# Power.net
KiCad netlist of a schematic drawn in Altium Designer
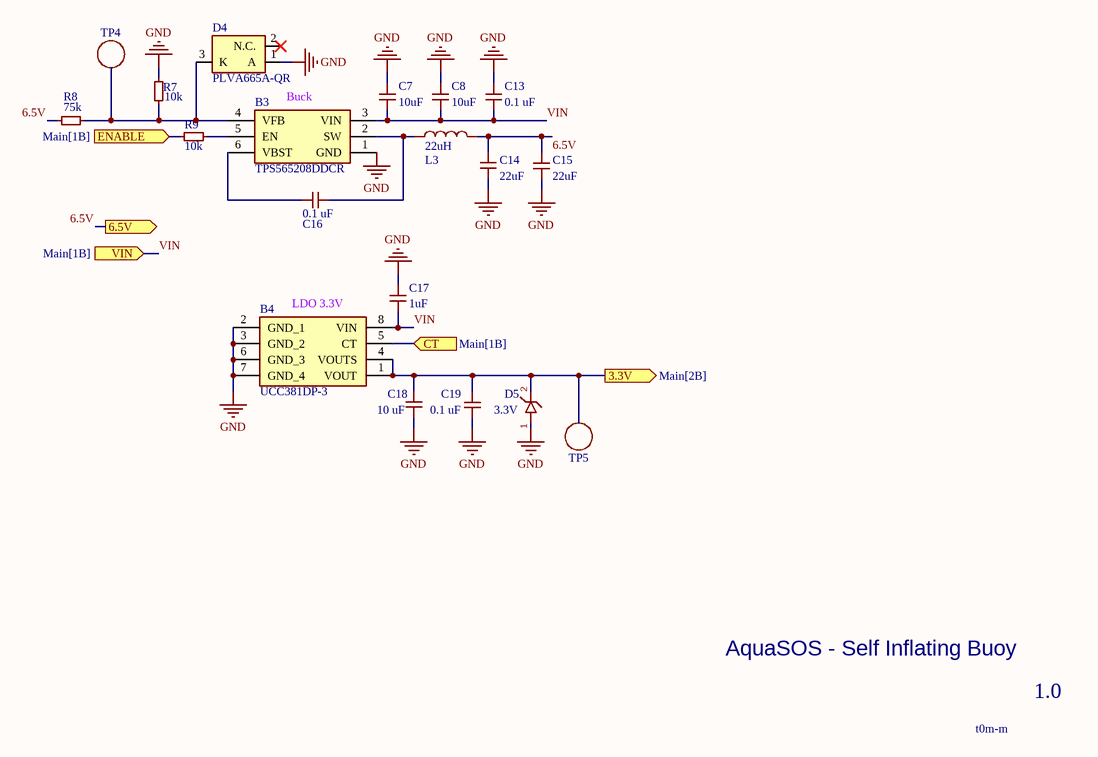
[diagram p0: Power.SchDoc]

(export (version "E")
  (design (tool "Eeschema 10.0.6"))
  (components
    (comp (ref "B3")
      (value "TPS565208DDCR")
      (footprint "SOT95P280X110-6N")
      (description "4.5V to 17V, 5A Synchronous Step-Down Voltage Regulator in SOT23")
      (fields (field (name "MOUSER PART NUMBER") "595-TPS565208DDCR"))
      (libsource (lib "Schlib1") (part "TPS565208DDCR"))
    )
    (comp (ref "B4")
      (value "UCC381DP-3")
      (footprint "UCC381DP-3-8N")
      (description "1-A, Low-Dropout Linear Regulator")
      (fields (field (name "MOUSER PART NUMBER") "595-UCC381DP-3"))
      (libsource (lib "Schlib1") (part "UCC381DP-3"))
    )
    (comp (ref "C7")
      (value "10uF")
      (footprint "CAPC2012X145N")
      (libsource (lib "Schlib1") (part "C0805X106K8RACAUTO7210"))
    )
    (comp (ref "C8")
      (value "10uF")
      (footprint "CAPC2012X145N")
      (libsource (lib "Schlib1") (part "C0805X106K8RACAUTO7210"))
    )
    (comp (ref "C13")
      (value "0.1 uF")
      (footprint "MLASU105SB7104KFNB25")
      (description "0.1uF Capacitor")
      (libsource (lib "Schlib1") (part "MLASU105SB7104KFNB25"))
    )
    (comp (ref "C14")
      (value "22uF")
      (footprint "CL31X226KPHN3NE")
      (description "CAP CER 22UF 10V X6S 1206")
      (libsource (lib "Schlib1") (part "CL31X226KPHN3NE"))
    )
    (comp (ref "C15")
      (value "22uF")
      (footprint "CL31X226KPHN3NE")
      (description "CAP CER 22UF 10V X6S 1206")
      (libsource (lib "Schlib1") (part "CL31X226KPHN3NE"))
    )
    (comp (ref "C16")
      (value "0.1 uF")
      (footprint "MLASU105SB7104KFNB25")
      (description "0.1uF Capacitor")
      (libsource (lib "Schlib1") (part "MLASU105SB7104KFNB25"))
    )
    (comp (ref "C17")
      (value "1uF")
      (footprint "MLASU105SB7104KFNB25")
      (description "1uF 0402 10V")
      (libsource (lib "Schlib1") (part "GRM155Z71A105KE01D"))
    )
    (comp (ref "C18")
      (value "10 uF")
      (footprint "KGM05CS60J106MH")
      (description "10 uF Capacitor")
      (libsource (lib "Schlib1") (part "KGM05CS60J106MH"))
    )
    (comp (ref "C19")
      (value "0.1 uF")
      (footprint "MLASU105SB7104KFNB25")
      (description "0.1uF Capacitor")
      (libsource (lib "Schlib1") (part "MLASU105SB7104KFNB25"))
    )
    (comp (ref "D4")
      (value "PLVA665A-QR")
      (footprint "PLVA665A-QR")
      (description "Zener Diode 6.5 V 250 mW +/-3.08% Surface Mount TO-236AB")
      (fields (field (name "MOUSER PART NUMBER") "771-PLVA665A-QR"))
      (libsource (lib "AquaSOS DevBoard") (part "PLVA665A-QR"))
    )
    (comp (ref "D5")
      (value "3.3V")
      (footprint "MMSZ5226C-HE3_A-08")
      (description "3.3V Zener Diode")
      (libsource (lib "AquaSOS DevBoard") (part "MMSZ5226C-HE3_A-08"))
    )
    (comp (ref "L3")
      (value "22uH")
      (footprint "SRR1240-3R3Y")
      (libsource (lib "Schlib1") (part "SRR1240-3R3Y"))
    )
    (comp (ref "R7")
      (value "10k")
      (footprint "CRCW040210K0FKEDC")
      (description "10k 0402 Resistor")
      (libsource (lib "") (part "CRCW040210K0FKEDC_1"))
    )
    (comp (ref "R8")
      (value "75k")
      (footprint "CRCW040210K0FKEDC")
      (libsource (lib "Schlib1") (part "RT73F1E75KBTH"))
    )
    (comp (ref "R9")
      (value "10k")
      (footprint "CRCW040210K0FKEDC")
      (description "10k 0402 Resistor")
      (libsource (lib "AquaSOS DevBoard") (part "CRCW040210K0FKEDC"))
    )
    (comp (ref "TP4")
      (value "TP")
      (footprint "Test Point")
      (description "Test Point")
      (libsource (lib "AquaSOS DevBoard") (part "Test Point"))
    )
    (comp (ref "TP5")
      (value "TP")
      (footprint "Test Point")
      (description "Test Point")
      (libsource (lib "AquaSOS DevBoard") (part "Test Point"))
    )
  )
  (nets
    (net (code "1") (name "/3.3V") (class "Default")
      (node (ref "B4") (pin "1") (pinfunction "VOUT_1") (pintype "passive"))
      (node (ref "B4") (pin "4") (pinfunction "VOUTS_4") (pintype "passive"))
      (node (ref "C18") (pin "1") (pinfunction "1_1") (pintype "passive"))
      (node (ref "C19") (pin "1") (pinfunction "1_1") (pintype "passive"))
      (node (ref "D5") (pin "2") (pinfunction "A_2") (pintype "passive"))
      (node (ref "TP5") (pin "1") (pinfunction "1_1") (pintype "passive"))
    )
    (net (code "2") (name "/6.5V") (class "Default")
      (node (ref "C14") (pin "1") (pinfunction "1_1") (pintype "passive"))
      (node (ref "C15") (pin "1") (pinfunction "1_1") (pintype "passive"))
      (node (ref "L3") (pin "2") (pinfunction "2_2") (pintype "passive"))
      (node (ref "R8") (pin "1") (pinfunction "1_1") (pintype "passive"))
    )
    (net (code "3") (name "/CT") (class "Default")
      (node (ref "B4") (pin "5") (pinfunction "CT_5") (pintype "passive"))
    )
    (net (code "4") (name "/ENABLE") (class "Default")
      (node (ref "R9") (pin "1") (pinfunction "1_1") (pintype "passive"))
    )
    (net (code "5") (name "/VIN") (class "Default")
      (node (ref "B3") (pin "3") (pinfunction "VIN_3") (pintype "passive"))
      (node (ref "B4") (pin "8") (pinfunction "VIN_8") (pintype "passive"))
      (node (ref "C13") (pin "2") (pinfunction "2_2") (pintype "passive"))
      (node (ref "C17") (pin "2") (pinfunction "2_2") (pintype "passive"))
      (node (ref "C7") (pin "1") (pinfunction "1_1") (pintype "passive"))
      (node (ref "C8") (pin "1") (pinfunction "1_1") (pintype "passive"))
    )
    (net (code "6") (name "GND") (class "Default")
      (node (ref "B3") (pin "1") (pinfunction "GND_1") (pintype "passive"))
      (node (ref "B4") (pin "2") (pinfunction "GND_1_2") (pintype "passive"))
      (node (ref "B4") (pin "3") (pinfunction "GND_2_3") (pintype "passive"))
      (node (ref "B4") (pin "6") (pinfunction "GND_3_6") (pintype "passive"))
      (node (ref "B4") (pin "7") (pinfunction "GND_4_7") (pintype "passive"))
      (node (ref "C13") (pin "1") (pinfunction "1_1") (pintype "passive"))
      (node (ref "C14") (pin "2") (pinfunction "2_2") (pintype "passive"))
      (node (ref "C15") (pin "2") (pinfunction "2_2") (pintype "passive"))
      (node (ref "C17") (pin "1") (pinfunction "1_1") (pintype "passive"))
      (node (ref "C18") (pin "2") (pinfunction "2_2") (pintype "passive"))
      (node (ref "C19") (pin "2") (pinfunction "2_2") (pintype "passive"))
      (node (ref "C7") (pin "2") (pinfunction "2_2") (pintype "passive"))
      (node (ref "C8") (pin "2") (pinfunction "2_2") (pintype "passive"))
      (node (ref "D4") (pin "1") (pinfunction "A_1") (pintype "passive"))
      (node (ref "D5") (pin "1") (pinfunction "K_1") (pintype "passive"))
      (node (ref "R7") (pin "1") (pinfunction "1_1") (pintype "passive"))
    )
    (net (code "7") (name "Net-(B3-EN)") (class "Default")
      (node (ref "B3") (pin "5") (pinfunction "EN_5") (pintype "passive"))
      (node (ref "R9") (pin "2") (pinfunction "2_2") (pintype "passive"))
    )
    (net (code "8") (name "Net-(B3-SW)") (class "Default")
      (node (ref "B3") (pin "2") (pinfunction "SW_2") (pintype "passive"))
      (node (ref "C16") (pin "2") (pinfunction "2_2") (pintype "passive"))
      (node (ref "L3") (pin "1") (pinfunction "1_1") (pintype "passive"))
    )
    (net (code "9") (name "Net-(B3-VBST)") (class "Default")
      (node (ref "B3") (pin "6") (pinfunction "VBST_6") (pintype "passive"))
      (node (ref "C16") (pin "1") (pinfunction "1_1") (pintype "passive"))
    )
    (net (code "10") (name "Net-(B3-VFB)") (class "Default")
      (node (ref "B3") (pin "4") (pinfunction "VFB_4") (pintype "passive"))
      (node (ref "D4") (pin "3") (pinfunction "K_3") (pintype "passive"))
      (node (ref "R7") (pin "2") (pinfunction "2_2") (pintype "passive"))
      (node (ref "R8") (pin "2") (pinfunction "2_2") (pintype "passive"))
      (node (ref "TP4") (pin "1") (pinfunction "1_1") (pintype "passive"))
    )
    (net (code "11") (name "unconnected-(D4-N.C.-Pad2)") (class "Default")
      (node (ref "D4") (pin "2") (pinfunction "N.C._2") (pintype "passive+no_connect"))
    )
  )
)
